# 4_-_MOTOR-DRIVER.net
KiCad netlist of a schematic drawn in Altium Designer
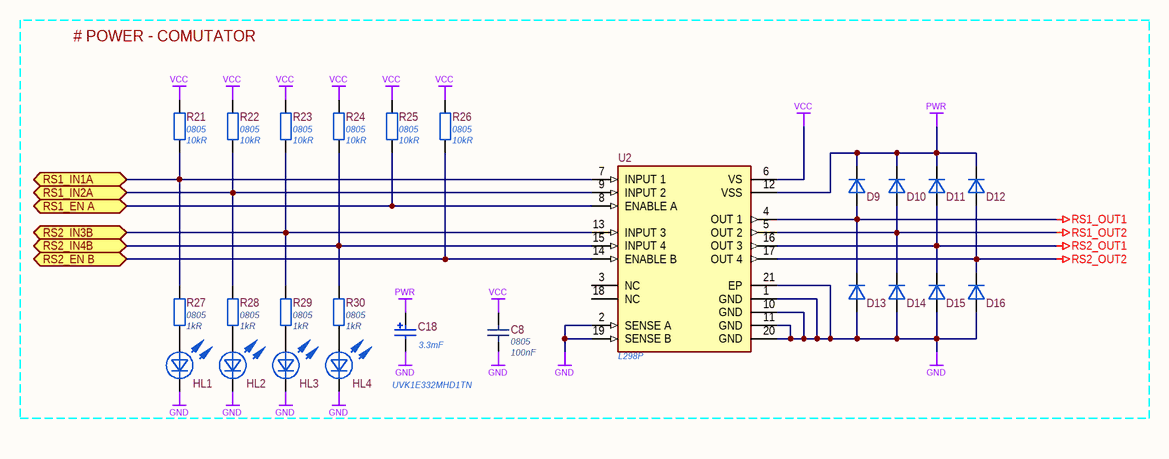
[diagram p0: [4] - MOTOR-DRIVER.SchDoc]

(export (version "E")
  (design (tool "Eeschema 10.0.6"))
  (components
    (comp (ref "C8")
      (value "AC0805KRX7R9BB104")
      (footprint "CH0805C")
      (description "0.10µF 50V Ceramic Capacitor X7R 0805 (2012 Metric) 0.079\" L x 0.049\" W (2.00mm x 1.25mm)")
      (fields
        (field (name "CASE/PACKAGE") "0805")
        (field (name "CAPACITANCE") "100nF")
        (field (name "TOLERANCE") "10%")
      )
      (libsource (lib "Chip Capacitors") (part "AC0805KRX7R9BB104"))
    )
    (comp (ref "C18")
      (value "UVK1E332MHD1TN")
      (footprint "El-d16-h26-F7.62")
      (description "CAP ALUM 3300UF 20% 25V RADIAL")
      (fields (field (name "CAPACITANCE") "3.3mF") (field (name "TOLERANCE") "20%"))
      (libsource (lib "Electrolytic Capacitors") (part "UVK1E332MHD1TN"))
    )
    (comp (ref "D9")
      (value "RS1MB-13-F")
      (footprint "SMB")
      (description "DIODE GEN PURP 1KV 1A SMB")
      (libsource (lib "Diodes") (part "RS1MB-13-F"))
    )
    (comp (ref "D10")
      (value "RS1MB-13-F")
      (footprint "SMB")
      (description "DIODE GEN PURP 1KV 1A SMB")
      (libsource (lib "Diodes") (part "RS1MB-13-F"))
    )
    (comp (ref "D11")
      (value "RS1MB-13-F")
      (footprint "SMB")
      (description "DIODE GEN PURP 1KV 1A SMB")
      (libsource (lib "Diodes") (part "RS1MB-13-F"))
    )
    (comp (ref "D12")
      (value "RS1MB-13-F")
      (footprint "SMB")
      (description "DIODE GEN PURP 1KV 1A SMB")
      (libsource (lib "Diodes") (part "RS1MB-13-F"))
    )
    (comp (ref "D13")
      (value "RS1MB-13-F")
      (footprint "SMB")
      (description "DIODE GEN PURP 1KV 1A SMB")
      (libsource (lib "Diodes") (part "RS1MB-13-F"))
    )
    (comp (ref "D14")
      (value "RS1MB-13-F")
      (footprint "SMB")
      (description "DIODE GEN PURP 1KV 1A SMB")
      (libsource (lib "Diodes") (part "RS1MB-13-F"))
    )
    (comp (ref "D15")
      (value "RS1MB-13-F")
      (footprint "SMB")
      (description "DIODE GEN PURP 1KV 1A SMB")
      (libsource (lib "Diodes") (part "RS1MB-13-F"))
    )
    (comp (ref "D16")
      (value "RS1MB-13-F")
      (footprint "SMB")
      (description "DIODE GEN PURP 1KV 1A SMB")
      (libsource (lib "Diodes") (part "RS1MB-13-F"))
    )
    (comp (ref "HL1")
      (value "SMLLXT0805GWTR")
      (footprint "CH0805LG")
      (description "GLOVE, POLYAMIDE, L/FREE, PU, SIZE 6 - More Details")
      (libsource (lib "LED") (part "SMLLXT0805GWTR"))
    )
    (comp (ref "HL2")
      (value "SMLLXT0805GWTR")
      (footprint "CH0805LG")
      (description "GLOVE, POLYAMIDE, L/FREE, PU, SIZE 6 - More Details")
      (libsource (lib "LED") (part "SMLLXT0805GWTR"))
    )
    (comp (ref "HL3")
      (value "SMLLXT0805GWTR")
      (footprint "CH0805LG")
      (description "GLOVE, POLYAMIDE, L/FREE, PU, SIZE 6 - More Details")
      (libsource (lib "LED") (part "SMLLXT0805GWTR"))
    )
    (comp (ref "HL4")
      (value "SMLLXT0805GWTR")
      (footprint "CH0805LG")
      (description "GLOVE, POLYAMIDE, L/FREE, PU, SIZE 6 - More Details")
      (libsource (lib "LED") (part "SMLLXT0805GWTR"))
    )
    (comp (ref "R21")
      (value "RC0805JR-0710KL")
      (footprint "CH0805R")
      (description "RES SMD 10K OHM 5% 1/8W 0805")
      (fields
        (field (name "CASE CODE (IMPERIAL)") "0805")
        (field (name "TOLERANCE") "5%")
        (field (name "RESISTANCE") "10kR")
      )
      (libsource (lib "Chip Resistors") (part "RC0805JR-0710KL"))
    )
    (comp (ref "R22")
      (value "RC0805JR-0710KL")
      (footprint "CH0805R")
      (description "RES SMD 10K OHM 5% 1/8W 0805")
      (fields
        (field (name "CASE CODE (IMPERIAL)") "0805")
        (field (name "TOLERANCE") "5%")
        (field (name "RESISTANCE") "10kR")
      )
      (libsource (lib "Chip Resistors") (part "RC0805JR-0710KL"))
    )
    (comp (ref "R23")
      (value "RC0805JR-0710KL")
      (footprint "CH0805R")
      (description "RES SMD 10K OHM 5% 1/8W 0805")
      (fields
        (field (name "CASE CODE (IMPERIAL)") "0805")
        (field (name "TOLERANCE") "5%")
        (field (name "RESISTANCE") "10kR")
      )
      (libsource (lib "Chip Resistors") (part "RC0805JR-0710KL"))
    )
    (comp (ref "R24")
      (value "RC0805JR-0710KL")
      (footprint "CH0805R")
      (description "RES SMD 10K OHM 5% 1/8W 0805")
      (fields
        (field (name "CASE CODE (IMPERIAL)") "0805")
        (field (name "TOLERANCE") "5%")
        (field (name "RESISTANCE") "10kR")
      )
      (libsource (lib "Chip Resistors") (part "RC0805JR-0710KL"))
    )
    (comp (ref "R25")
      (value "RC0805JR-0710KL")
      (footprint "CH0805R")
      (description "RES SMD 10K OHM 5% 1/8W 0805")
      (fields
        (field (name "CASE CODE (IMPERIAL)") "0805")
        (field (name "TOLERANCE") "5%")
        (field (name "RESISTANCE") "10kR")
      )
      (libsource (lib "Chip Resistors") (part "RC0805JR-0710KL"))
    )
    (comp (ref "R26")
      (value "RC0805JR-0710KL")
      (footprint "CH0805R")
      (description "RES SMD 10K OHM 5% 1/8W 0805")
      (fields
        (field (name "CASE CODE (IMPERIAL)") "0805")
        (field (name "TOLERANCE") "5%")
        (field (name "RESISTANCE") "10kR")
      )
      (libsource (lib "Chip Resistors") (part "RC0805JR-0710KL"))
    )
    (comp (ref "R27")
      (value "RC0805JR-071KL")
      (footprint "CH0805R")
      (description "RES SMD 1K OHM 5% 1/8W 0805")
      (fields
        (field (name "CASE CODE (IMPERIAL)") "0805")
        (field (name "RESISTANCE") "1kR")
        (field (name "TOLERANCE") "5%")
      )
      (libsource (lib "Chip Resistors") (part "RC0805JR-071KL"))
    )
    (comp (ref "R28")
      (value "RC0805JR-071KL")
      (footprint "CH0805R")
      (description "RES SMD 1K OHM 5% 1/8W 0805")
      (fields
        (field (name "CASE CODE (IMPERIAL)") "0805")
        (field (name "RESISTANCE") "1kR")
        (field (name "TOLERANCE") "5%")
      )
      (libsource (lib "Chip Resistors") (part "RC0805JR-071KL"))
    )
    (comp (ref "R29")
      (value "RC0805JR-071KL")
      (footprint "CH0805R")
      (description "RES SMD 1K OHM 5% 1/8W 0805")
      (fields
        (field (name "CASE CODE (IMPERIAL)") "0805")
        (field (name "RESISTANCE") "1kR")
        (field (name "TOLERANCE") "5%")
      )
      (libsource (lib "Chip Resistors") (part "RC0805JR-071KL"))
    )
    (comp (ref "R30")
      (value "RC0805JR-071KL")
      (footprint "CH0805R")
      (description "RES SMD 1K OHM 5% 1/8W 0805")
      (fields
        (field (name "CASE CODE (IMPERIAL)") "0805")
        (field (name "RESISTANCE") "1kR")
        (field (name "TOLERANCE") "5%")
      )
      (libsource (lib "Chip Resistors") (part "RC0805JR-071KL"))
    )
    (comp (ref "U2")
      (value "L298P")
      (footprint "STM-PowerSO20_N")
      (description "IC BRIDGE DRIVER PAR 20POWERSO")
      (libsource (lib "Drivers") (part "L298P"))
    )
  )
  (nets
    (net (code "1") (name "/RS1_EN A") (class "Default")
      (node (ref "R25") (pin "1") (pinfunction "1_1") (pintype "passive"))
      (node (ref "U2") (pin "8") (pinfunction "ENABLE_A_8") (pintype "input"))
    )
    (net (code "2") (name "/RS1_IN1A") (class "Default")
      (node (ref "R21") (pin "1") (pinfunction "1_1") (pintype "passive"))
      (node (ref "R27") (pin "2") (pinfunction "2_2") (pintype "passive"))
      (node (ref "U2") (pin "7") (pinfunction "INPUT_1_7") (pintype "input"))
    )
    (net (code "3") (name "/RS1_IN2A") (class "Default")
      (node (ref "R22") (pin "1") (pinfunction "1_1") (pintype "passive"))
      (node (ref "R28") (pin "2") (pinfunction "2_2") (pintype "passive"))
      (node (ref "U2") (pin "9") (pinfunction "INPUT_2_9") (pintype "input"))
    )
    (net (code "4") (name "/RS2_EN B") (class "Default")
      (node (ref "R26") (pin "1") (pinfunction "1_1") (pintype "passive"))
      (node (ref "U2") (pin "14") (pinfunction "ENABLE_B_14") (pintype "input"))
    )
    (net (code "5") (name "/RS2_IN3B") (class "Default")
      (node (ref "R23") (pin "1") (pinfunction "1_1") (pintype "passive"))
      (node (ref "R29") (pin "2") (pinfunction "2_2") (pintype "passive"))
      (node (ref "U2") (pin "13") (pinfunction "INPUT_3_13") (pintype "input"))
    )
    (net (code "6") (name "/RS2_IN4B") (class "Default")
      (node (ref "R24") (pin "1") (pinfunction "1_1") (pintype "passive"))
      (node (ref "R30") (pin "2") (pinfunction "2_2") (pintype "passive"))
      (node (ref "U2") (pin "15") (pinfunction "INPUT_4_15") (pintype "input"))
    )
    (net (code "7") (name "GND") (class "Default")
      (node (ref "C18") (pin "2") (pinfunction "2_2") (pintype "passive"))
      (node (ref "C8") (pin "2") (pinfunction "2_2") (pintype "passive"))
      (node (ref "D13") (pin "1") (pinfunction "A_1") (pintype "passive"))
      (node (ref "D14") (pin "1") (pinfunction "A_1") (pintype "passive"))
      (node (ref "D15") (pin "1") (pinfunction "A_1") (pintype "passive"))
      (node (ref "D16") (pin "1") (pinfunction "A_1") (pintype "passive"))
      (node (ref "HL1") (pin "2") (pinfunction "K_2") (pintype "passive"))
      (node (ref "HL2") (pin "2") (pinfunction "K_2") (pintype "passive"))
      (node (ref "HL3") (pin "2") (pinfunction "K_2") (pintype "passive"))
      (node (ref "HL4") (pin "2") (pinfunction "K_2") (pintype "passive"))
      (node (ref "U2") (pin "1") (pinfunction "GND_1") (pintype "power_in"))
      (node (ref "U2") (pin "10") (pinfunction "GND_10") (pintype "power_in"))
      (node (ref "U2") (pin "11") (pinfunction "GND_11") (pintype "power_in"))
      (node (ref "U2") (pin "19") (pinfunction "SENSE_B_19") (pintype "input"))
      (node (ref "U2") (pin "2") (pinfunction "SENSE_A_2") (pintype "input"))
      (node (ref "U2") (pin "20") (pinfunction "GND_20") (pintype "power_in"))
      (node (ref "U2") (pin "21") (pinfunction "EP_21") (pintype "power_in"))
    )
    (net (code "8") (name "Net-(HL1-A)") (class "Default")
      (node (ref "HL1") (pin "1") (pinfunction "A_1") (pintype "passive"))
      (node (ref "R27") (pin "1") (pinfunction "1_1") (pintype "passive"))
    )
    (net (code "9") (name "Net-(HL2-A)") (class "Default")
      (node (ref "HL2") (pin "1") (pinfunction "A_1") (pintype "passive"))
      (node (ref "R28") (pin "1") (pinfunction "1_1") (pintype "passive"))
    )
    (net (code "10") (name "Net-(HL3-A)") (class "Default")
      (node (ref "HL3") (pin "1") (pinfunction "A_1") (pintype "passive"))
      (node (ref "R29") (pin "1") (pinfunction "1_1") (pintype "passive"))
    )
    (net (code "11") (name "Net-(HL4-A)") (class "Default")
      (node (ref "HL4") (pin "1") (pinfunction "A_1") (pintype "passive"))
      (node (ref "R30") (pin "1") (pinfunction "1_1") (pintype "passive"))
    )
    (net (code "12") (name "PWR") (class "Default")
      (node (ref "C18") (pin "1") (pinfunction "1_1") (pintype "passive"))
      (node (ref "D10") (pin "2") (pinfunction "K_2") (pintype "passive"))
      (node (ref "D11") (pin "2") (pinfunction "K_2") (pintype "passive"))
      (node (ref "D12") (pin "2") (pinfunction "K_2") (pintype "passive"))
      (node (ref "D9") (pin "2") (pinfunction "K_2") (pintype "passive"))
      (node (ref "U2") (pin "12") (pinfunction "VSS_12") (pintype "power_in"))
    )
    (net (code "13") (name "RS1_OUT1") (class "Default")
      (node (ref "D13") (pin "2") (pinfunction "K_2") (pintype "passive"))
      (node (ref "D9") (pin "1") (pinfunction "A_1") (pintype "passive"))
      (node (ref "U2") (pin "4") (pinfunction "OUT_1_4") (pintype "output"))
    )
    (net (code "14") (name "RS1_OUT2") (class "Default")
      (node (ref "D10") (pin "1") (pinfunction "A_1") (pintype "passive"))
      (node (ref "D14") (pin "2") (pinfunction "K_2") (pintype "passive"))
      (node (ref "U2") (pin "5") (pinfunction "OUT_2_5") (pintype "output"))
    )
    (net (code "15") (name "RS2_OUT1") (class "Default")
      (node (ref "D11") (pin "1") (pinfunction "A_1") (pintype "passive"))
      (node (ref "D15") (pin "2") (pinfunction "K_2") (pintype "passive"))
      (node (ref "U2") (pin "16") (pinfunction "OUT_3_16") (pintype "output"))
    )
    (net (code "16") (name "RS2_OUT2") (class "Default")
      (node (ref "D12") (pin "1") (pinfunction "A_1") (pintype "passive"))
      (node (ref "D16") (pin "2") (pinfunction "K_2") (pintype "passive"))
      (node (ref "U2") (pin "17") (pinfunction "OUT_4_17") (pintype "output"))
    )
    (net (code "17") (name "VCC") (class "Default")
      (node (ref "C8") (pin "1") (pinfunction "1_1") (pintype "passive"))
      (node (ref "R21") (pin "2") (pinfunction "2_2") (pintype "passive"))
      (node (ref "R22") (pin "2") (pinfunction "2_2") (pintype "passive"))
      (node (ref "R23") (pin "2") (pinfunction "2_2") (pintype "passive"))
      (node (ref "R24") (pin "2") (pinfunction "2_2") (pintype "passive"))
      (node (ref "R25") (pin "2") (pinfunction "2_2") (pintype "passive"))
      (node (ref "R26") (pin "2") (pinfunction "2_2") (pintype "passive"))
      (node (ref "U2") (pin "6") (pinfunction "VS_6") (pintype "power_in"))
    )
    (net (code "18") (name "unconnected-(U2-NC-Pad3)") (class "Default")
      (node (ref "U2") (pin "3") (pinfunction "NC_3") (pintype "passive"))
    )
    (net (code "19") (name "unconnected-(U2-NC-Pad18)") (class "Default")
      (node (ref "U2") (pin "18") (pinfunction "NC_18") (pintype "passive"))
    )
  )
)
